# AC_circuit.net
KiCad netlist of a schematic drawn in Altium Designer
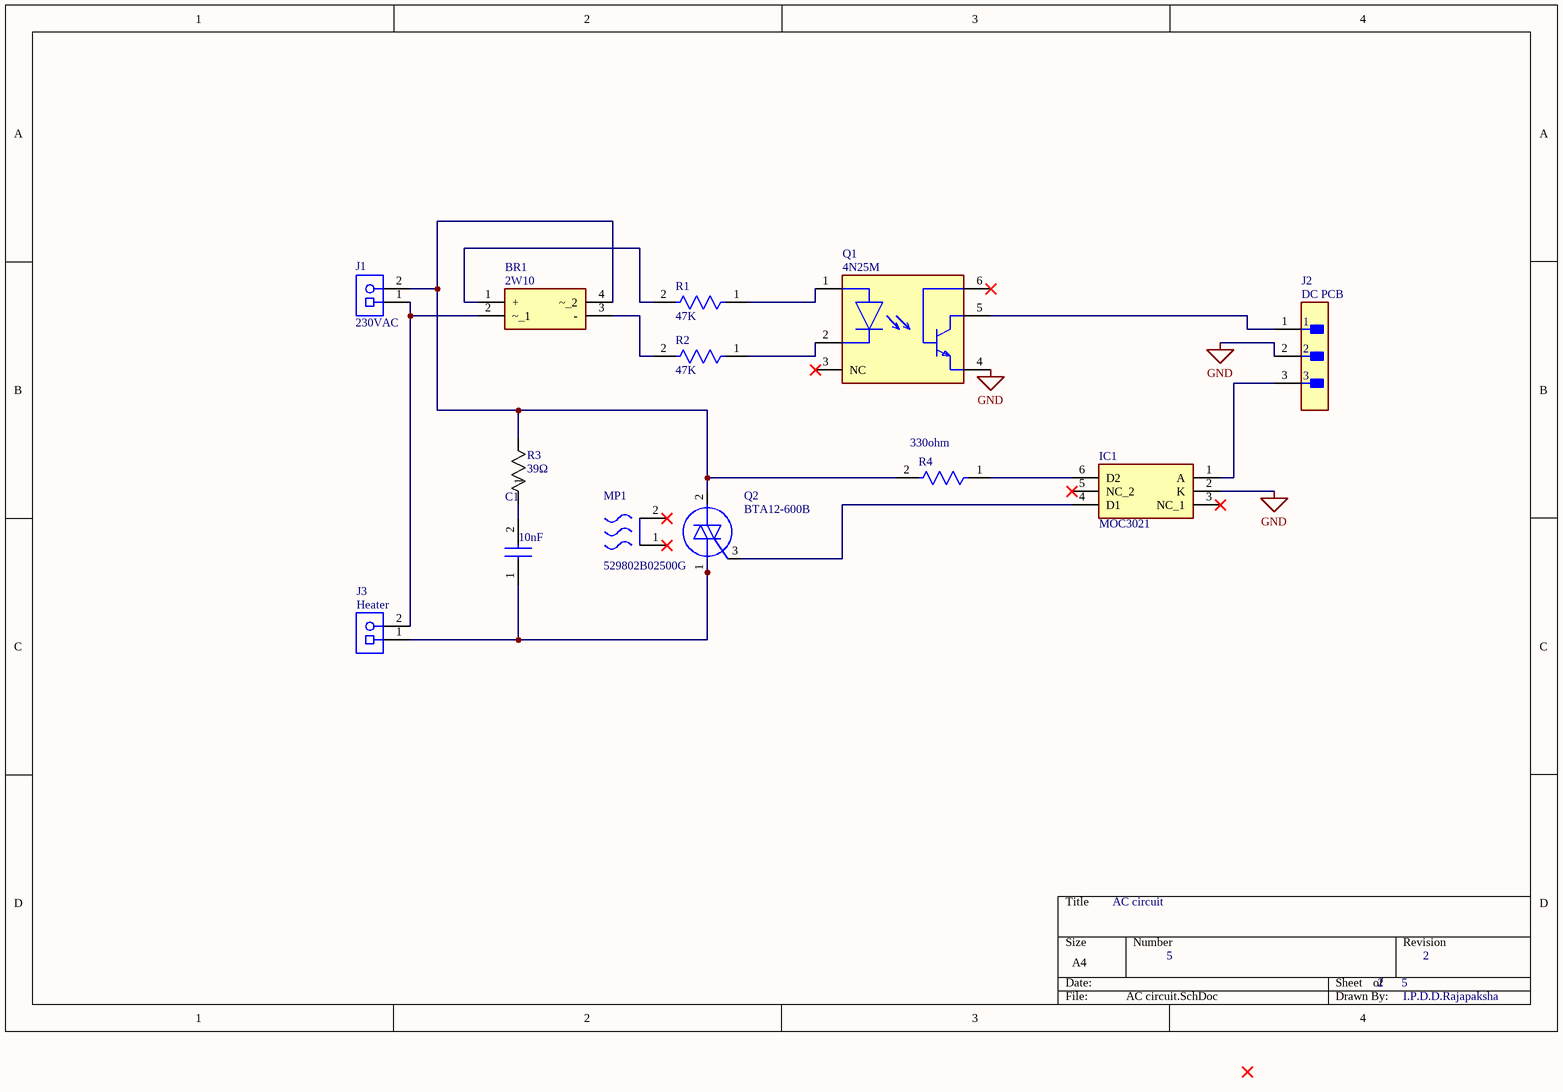
[diagram p0: AC circuit.SchDoc]

(export (version "E")
  (design (tool "Eeschema 10.0.6"))
  (components
    (comp (ref "BR1")
      (value "2W10")
      (footprint "SamacSys:2W10")
      (description "Bridge Rectifier")
      (libsource (lib "*") (part "2W10"))
    )
    (comp (ref "C1")
      (value "DE2E3SA103MA3BY02F")
      (footprint "SamacSys:DE2E3SA103MA3BY02F")
      (description "Capacitor")
      (fields (field (name "MOUSER PART NUMBER") "81-DE2E3SA103MA3BY2F") (field (name "PARAMETER 1") "10nF"))
      (libsource (lib "*") (part "DE2E3SA103MA3BY02F"))
    )
    (comp (ref "IC1")
      (value "MOC3021")
      (footprint "SamacSys:DIP762W50P254L712H450Q6N")
      (description "Integrated Circuit")
      (libsource (lib "*") (part "MOC3021"))
    )
    (comp (ref "J1")
      (value "1729128")
      (footprint "PHOE-1729128-2_V")
      (description "PCB Terminal Block, 13.5 A, 400 V, 2-Pin THD, RoHS, Bulk")
      (fields (field (name "MANUFACTURER") "Phoenix Contact") (field (name "PARAMETER 1") "230VAC"))
      (libsource (lib "Altium Content Vault") (part "CN-2P-F-R2"))
    )
    (comp (ref "J2")
      (value "B3B-XH-AM(LF)(SN)")
      (footprint "FP-B3B-XH-AM_LF_SN-MFG")
      (description "CONN HEADER VERT 3POS 2.5MM")
      (fields (field (name "PARAMETER 1") "DC PCB"))
      (libsource (lib "Altium Content Vault") (part "0d3f023dd272f625e17a2be33dea85f"))
    )
    (comp (ref "J3")
      (value "1729128")
      (footprint "PHOE-1729128-2_V")
      (description "PCB Terminal Block, 13.5 A, 400 V, 2-Pin THD, RoHS, Bulk")
      (fields (field (name "MANUFACTURER") "Phoenix Contact") (field (name "PARAMETER 1") "Heater"))
      (libsource (lib "Altium Content Vault") (part "CN-2P-F-R2"))
    )
    (comp (ref "MP1")
      (value "529802B02500G")
      (footprint "FP-529802B02500G-MFG")
      (description "HEATSINK TO-220 W/PINS 1.5\"TALL")
      (libsource (lib "Altium Content Vault") (part "57ddec3899b3862ad90e358acd4ccaf"))
    )
    (comp (ref "Q1")
      (value "4N25M")
      (footprint "FP-646BX-MFG")
      (description "4N25M Optocoupler DC-IN 1-CH Transistor With Base DC-OUT 6-Pin PDIP Tube - Bulk")
      (libsource (lib "Altium Content Vault") (part "60cd882971725889b330b3d3aa4682b"))
    )
    (comp (ref "Q2")
      (value "BTA12-600B")
      (footprint "SamacSys:TO255P460X1020X1965-3P")
      (description "Triac")
      (libsource (lib "*") (part "BTA12-600B"))
    )
    (comp (ref "R1")
      (value "47K")
      (footprint "FP-CMF50-0")
      (description "CMF5073K200FHEB Res Metal Film 73.2K Ohm 1% 0.125W(1/8W) ±50ppm/°C Epoxy AXL T/R")
      (fields (field (name "TOLERANCE") "1%") (field (name "Comment") "CMF5073K200FHEB"))
      (libsource (lib "Altium Content Vault") (part "1029c3af85768c4190bb7ad29bc67b5"))
    )
    (comp (ref "R2")
      (value "47K")
      (footprint "FP-CMF50-0")
      (description "CMF5073K200FHEB Res Metal Film 73.2K Ohm 1% 0.125W(1/8W) ±50ppm/°C Epoxy AXL T/R")
      (fields (field (name "TOLERANCE") "1%") (field (name "Comment") "CMF5073K200FHEB"))
      (libsource (lib "Altium Content Vault") (part "1029c3af85768c4190bb7ad29bc67b5"))
    )
    (comp (ref "R3")
      (value "AC03000003909JAC00")
      (footprint "RES_AC03_VIS")
      (description "AC03000003909JAC00 AC03 Series Axial Wirewound Resistor 39Ohms +/-5% 3W -80 - -10ppm/degC")
      (fields (field (name "RESISTANCE") "39Ω") (field (name "TOLERANCE") "5%"))
      (libsource (lib "Altium Content Vault") (part "AC03000003909JAC00"))
    )
    (comp (ref "R4")
      (value "330ohm")
      (footprint "FP-CMF50-0")
      (description "CMF5073K200FHEB Res Metal Film 73.2K Ohm 1% 0.125W(1/8W) ±50ppm/°C Epoxy AXL T/R")
      (fields (field (name "TOLERANCE") "1%") (field (name "Comment") "CMF5073K200FHEB"))
      (libsource (lib "Altium Content Vault") (part "1029c3af85768c4190bb7ad29bc67b5"))
    )
  )
  (nets
    (net (code "1") (name "GND") (class "Default")
      (node (ref "IC1") (pin "2") (pinfunction "K_2") (pintype "passive"))
      (node (ref "J2") (pin "2") (pinfunction "2_2") (pintype "passive"))
      (node (ref "Q1") (pin "4") (pinfunction "E_4") (pintype "passive"))
    )
    (net (code "2") (name "Net-(BR1-+)") (class "Default")
      (node (ref "BR1") (pin "1") (pinfunction "+_1") (pintype "passive"))
      (node (ref "R1") (pin "2") (pinfunction "2_2") (pintype "passive"))
    )
    (net (code "3") (name "Net-(BR1--)") (class "Default")
      (node (ref "BR1") (pin "3") (pinfunction "-_3") (pintype "passive"))
      (node (ref "R2") (pin "2") (pinfunction "2_2") (pintype "passive"))
    )
    (net (code "4") (name "Net-(BR1-~_1)") (class "Default")
      (node (ref "BR1") (pin "2") (pinfunction "~_1_2") (pintype "passive"))
      (node (ref "J1") (pin "1") (pinfunction "1_1") (pintype "passive"))
      (node (ref "J3") (pin "2") (pinfunction "2_2") (pintype "passive"))
    )
    (net (code "5") (name "Net-(BR1-~_2)") (class "Default")
      (node (ref "BR1") (pin "4") (pinfunction "~_2_4") (pintype "passive"))
      (node (ref "J1") (pin "2") (pinfunction "2_2") (pintype "passive"))
      (node (ref "Q2") (pin "2") (pinfunction "MT2_2") (pintype "passive"))
      (node (ref "R3") (pin "2") (pinfunction "2_2") (pintype "passive"))
      (node (ref "R4") (pin "2") (pinfunction "2_2") (pintype "passive"))
    )
    (net (code "6") (name "Net-(C1-Pad2)") (class "Default")
      (node (ref "C1") (pin "2") (pinfunction "2_2") (pintype "passive"))
      (node (ref "R3") (pin "1") (pinfunction "1_1") (pintype "passive"))
    )
    (net (code "7") (name "Net-(IC1-A)") (class "Default")
      (node (ref "IC1") (pin "1") (pinfunction "A_1") (pintype "passive"))
      (node (ref "J2") (pin "3") (pinfunction "3_3") (pintype "passive"))
    )
    (net (code "8") (name "Net-(IC1-D1)") (class "Default")
      (node (ref "IC1") (pin "4") (pinfunction "D1_4") (pintype "passive"))
      (node (ref "Q2") (pin "3") (pinfunction "G_3") (pintype "passive"))
    )
    (net (code "9") (name "Net-(IC1-D2)") (class "Default")
      (node (ref "IC1") (pin "6") (pinfunction "D2_6") (pintype "passive"))
      (node (ref "R4") (pin "1") (pinfunction "1_1") (pintype "passive"))
    )
    (net (code "10") (name "Net-(J2-Pad1)") (class "Default")
      (node (ref "J2") (pin "1") (pinfunction "1_1") (pintype "passive"))
      (node (ref "Q1") (pin "5") (pinfunction "C_5") (pintype "passive"))
    )
    (net (code "11") (name "Net-(Q1-A)") (class "Default")
      (node (ref "Q1") (pin "1") (pinfunction "A_1") (pintype "passive"))
      (node (ref "R1") (pin "1") (pinfunction "1_1") (pintype "passive"))
    )
    (net (code "12") (name "Net-(Q1-C-Pad2)") (class "Default")
      (node (ref "Q1") (pin "2") (pinfunction "C_2") (pintype "passive"))
      (node (ref "R2") (pin "1") (pinfunction "1_1") (pintype "passive"))
    )
    (net (code "13") (name "Net-(Q2-MT1)") (class "Default")
      (node (ref "C1") (pin "1") (pinfunction "1_1") (pintype "passive"))
      (node (ref "J3") (pin "1") (pinfunction "1_1") (pintype "passive"))
      (node (ref "Q2") (pin "1") (pinfunction "MT1_1") (pintype "passive"))
    )
    (net (code "14") (name "unconnected-(IC1-NC_1-Pad3)") (class "Default")
      (node (ref "IC1") (pin "3") (pinfunction "NC_1_3") (pintype "passive+no_connect"))
    )
    (net (code "15") (name "unconnected-(IC1-NC_2-Pad5)") (class "Default")
      (node (ref "IC1") (pin "5") (pinfunction "NC_2_5") (pintype "passive+no_connect"))
    )
    (net (code "16") (name "unconnected-(MP1-MNT_1-Pad1)") (class "Default")
      (node (ref "MP1") (pin "1") (pinfunction "MNT_1_1") (pintype "passive+no_connect"))
    )
    (net (code "17") (name "unconnected-(MP1-MNT_2-Pad2)") (class "Default")
      (node (ref "MP1") (pin "2") (pinfunction "MNT_2_2") (pintype "passive+no_connect"))
    )
    (net (code "18") (name "unconnected-(Q1-B-Pad6)") (class "Default")
      (node (ref "Q1") (pin "6") (pinfunction "B_6") (pintype "passive+no_connect"))
    )
    (net (code "19") (name "unconnected-(Q1-NC-Pad3)") (class "Default")
      (node (ref "Q1") (pin "3") (pinfunction "NC_3") (pintype "passive+no_connect"))
    )
  )
)
